# GateWay-NRF-version-puissance.net
KiCad netlist of a schematic drawn in Altium Designer
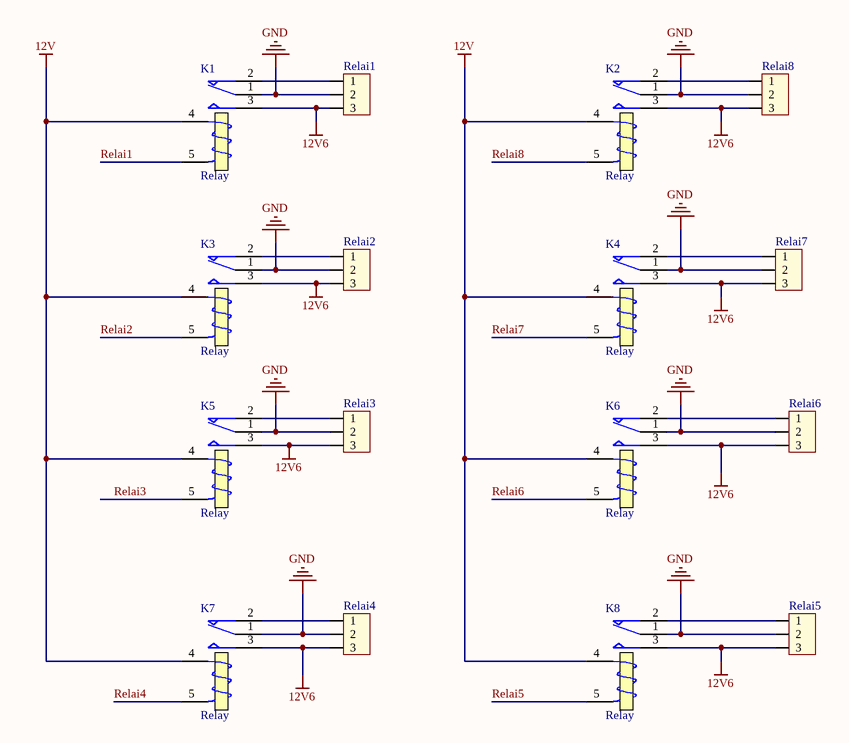
[diagram p0: GateWay-NRF-version-puissance.SchDoc]

(export (version "E")
  (design (tool "Eeschema 10.0.6"))
  (components
    (comp (ref "K1")
      (value "Relay")
      (footprint "MODULE5B")
      (description "SPDT Relay")
      (fields (field (name "PUBLISHER") "Altium Limited"))
      (libsource (lib "Miscellaneous Devices") (part "Relay"))
    )
    (comp (ref "K2")
      (value "Relay")
      (footprint "MODULE5B")
      (description "SPDT Relay")
      (fields (field (name "PUBLISHER") "Altium Limited"))
      (libsource (lib "Miscellaneous Devices") (part "Relay"))
    )
    (comp (ref "K3")
      (value "Relay")
      (footprint "MODULE5B")
      (description "SPDT Relay")
      (fields (field (name "PUBLISHER") "Altium Limited"))
      (libsource (lib "Miscellaneous Devices") (part "Relay"))
    )
    (comp (ref "K4")
      (value "Relay")
      (footprint "MODULE5B")
      (description "SPDT Relay")
      (fields (field (name "PUBLISHER") "Altium Limited"))
      (libsource (lib "Miscellaneous Devices") (part "Relay"))
    )
    (comp (ref "K5")
      (value "Relay")
      (footprint "MODULE5B")
      (description "SPDT Relay")
      (fields (field (name "PUBLISHER") "Altium Limited"))
      (libsource (lib "Miscellaneous Devices") (part "Relay"))
    )
    (comp (ref "K6")
      (value "Relay")
      (footprint "MODULE5B")
      (description "SPDT Relay")
      (fields (field (name "PUBLISHER") "Altium Limited"))
      (libsource (lib "Miscellaneous Devices") (part "Relay"))
    )
    (comp (ref "K7")
      (value "Relay")
      (footprint "MODULE5B")
      (description "SPDT Relay")
      (fields (field (name "PUBLISHER") "Altium Limited"))
      (libsource (lib "Miscellaneous Devices") (part "Relay"))
    )
    (comp (ref "K8")
      (value "Relay")
      (footprint "MODULE5B")
      (description "SPDT Relay")
      (fields (field (name "PUBLISHER") "Altium Limited"))
      (libsource (lib "Miscellaneous Devices") (part "Relay"))
    )
    (comp (ref "Relai1")
      (value "Header 3")
      (footprint "HED3")
      (description "Header 3 (Green)")
      (libsource (lib "hanguyen") (part "Hed3"))
    )
    (comp (ref "Relai2")
      (value "Header 3")
      (footprint "HED3")
      (description "Header 3 (Green)")
      (libsource (lib "hanguyen") (part "Hed3"))
    )
    (comp (ref "Relai3")
      (value "Header 3")
      (footprint "HED3")
      (description "Header 3 (Green)")
      (libsource (lib "hanguyen") (part "Hed3"))
    )
    (comp (ref "Relai4")
      (value "Header 3")
      (footprint "HED3")
      (description "Header 3 (Green)")
      (libsource (lib "hanguyen") (part "Hed3"))
    )
    (comp (ref "Relai5")
      (value "Header 3")
      (footprint "HED3")
      (description "Header 3 (Green)")
      (libsource (lib "hanguyen") (part "Hed3"))
    )
    (comp (ref "Relai6")
      (value "Header 3")
      (footprint "HED3")
      (description "Header 3 (Green)")
      (libsource (lib "hanguyen") (part "Hed3"))
    )
    (comp (ref "Relai7")
      (value "Header 3")
      (footprint "HED3")
      (description "Header 3 (Green)")
      (libsource (lib "hanguyen") (part "Hed3"))
    )
    (comp (ref "Relai8")
      (value "Header 3")
      (footprint "HED3")
      (description "Header 3 (Green)")
      (libsource (lib "hanguyen") (part "Hed3"))
    )
  )
  (nets
    (net (code "1") (name "/Relai1") (class "Default")
      (node (ref "K1") (pin "5") (pinfunction "T2_5") (pintype "passive"))
    )
    (net (code "2") (name "/Relai2") (class "Default")
      (node (ref "K3") (pin "5") (pinfunction "T2_5") (pintype "passive"))
    )
    (net (code "3") (name "/Relai3") (class "Default")
      (node (ref "K5") (pin "5") (pinfunction "T2_5") (pintype "passive"))
    )
    (net (code "4") (name "/Relai4") (class "Default")
      (node (ref "K7") (pin "5") (pinfunction "T2_5") (pintype "passive"))
    )
    (net (code "5") (name "/Relai5") (class "Default")
      (node (ref "K8") (pin "5") (pinfunction "T2_5") (pintype "passive"))
    )
    (net (code "6") (name "/Relai6") (class "Default")
      (node (ref "K6") (pin "5") (pinfunction "T2_5") (pintype "passive"))
    )
    (net (code "7") (name "/Relai7") (class "Default")
      (node (ref "K4") (pin "5") (pinfunction "T2_5") (pintype "passive"))
    )
    (net (code "8") (name "/Relai8") (class "Default")
      (node (ref "K2") (pin "5") (pinfunction "T2_5") (pintype "passive"))
    )
    (net (code "9") (name "12V") (class "Default")
      (node (ref "K1") (pin "4") (pinfunction "T1_4") (pintype "passive"))
      (node (ref "K2") (pin "4") (pinfunction "T1_4") (pintype "passive"))
      (node (ref "K3") (pin "4") (pinfunction "T1_4") (pintype "passive"))
      (node (ref "K4") (pin "4") (pinfunction "T1_4") (pintype "passive"))
      (node (ref "K5") (pin "4") (pinfunction "T1_4") (pintype "passive"))
      (node (ref "K6") (pin "4") (pinfunction "T1_4") (pintype "passive"))
      (node (ref "K7") (pin "4") (pinfunction "T1_4") (pintype "passive"))
      (node (ref "K8") (pin "4") (pinfunction "T1_4") (pintype "passive"))
    )
    (net (code "10") (name "12V6") (class "Default")
      (node (ref "K1") (pin "3") (pinfunction "NO_3") (pintype "passive"))
      (node (ref "K2") (pin "3") (pinfunction "NO_3") (pintype "passive"))
      (node (ref "K3") (pin "3") (pinfunction "NO_3") (pintype "passive"))
      (node (ref "K4") (pin "3") (pinfunction "NO_3") (pintype "passive"))
      (node (ref "K5") (pin "3") (pinfunction "NO_3") (pintype "passive"))
      (node (ref "K6") (pin "3") (pinfunction "NO_3") (pintype "passive"))
      (node (ref "K7") (pin "3") (pinfunction "NO_3") (pintype "passive"))
      (node (ref "K8") (pin "3") (pinfunction "NO_3") (pintype "passive"))
      (node (ref "Relai1") (pin "3") (pinfunction "3_3") (pintype "passive"))
      (node (ref "Relai2") (pin "3") (pinfunction "3_3") (pintype "passive"))
      (node (ref "Relai3") (pin "3") (pinfunction "3_3") (pintype "passive"))
      (node (ref "Relai4") (pin "3") (pinfunction "3_3") (pintype "passive"))
      (node (ref "Relai5") (pin "3") (pinfunction "3_3") (pintype "passive"))
      (node (ref "Relai6") (pin "3") (pinfunction "3_3") (pintype "passive"))
      (node (ref "Relai7") (pin "3") (pinfunction "3_3") (pintype "passive"))
      (node (ref "Relai8") (pin "3") (pinfunction "3_3") (pintype "passive"))
    )
    (net (code "11") (name "GND") (class "Default")
      (node (ref "K1") (pin "1") (pinfunction "COM_1") (pintype "passive"))
      (node (ref "K2") (pin "1") (pinfunction "COM_1") (pintype "passive"))
      (node (ref "K3") (pin "1") (pinfunction "COM_1") (pintype "passive"))
      (node (ref "K4") (pin "1") (pinfunction "COM_1") (pintype "passive"))
      (node (ref "K5") (pin "1") (pinfunction "COM_1") (pintype "passive"))
      (node (ref "K6") (pin "1") (pinfunction "COM_1") (pintype "passive"))
      (node (ref "K7") (pin "1") (pinfunction "COM_1") (pintype "passive"))
      (node (ref "K8") (pin "1") (pinfunction "COM_1") (pintype "passive"))
      (node (ref "Relai1") (pin "2") (pinfunction "2_2") (pintype "passive"))
      (node (ref "Relai2") (pin "2") (pinfunction "2_2") (pintype "passive"))
      (node (ref "Relai3") (pin "2") (pinfunction "2_2") (pintype "passive"))
      (node (ref "Relai4") (pin "2") (pinfunction "2_2") (pintype "passive"))
      (node (ref "Relai5") (pin "2") (pinfunction "2_2") (pintype "passive"))
      (node (ref "Relai6") (pin "2") (pinfunction "2_2") (pintype "passive"))
      (node (ref "Relai7") (pin "2") (pinfunction "2_2") (pintype "passive"))
      (node (ref "Relai8") (pin "2") (pinfunction "2_2") (pintype "passive"))
    )
    (net (code "12") (name "Net-(K1-NC)") (class "Default")
      (node (ref "K1") (pin "2") (pinfunction "NC_2") (pintype "passive"))
      (node (ref "Relai1") (pin "1") (pinfunction "1_1") (pintype "passive"))
    )
    (net (code "13") (name "Net-(K2-NC)") (class "Default")
      (node (ref "K2") (pin "2") (pinfunction "NC_2") (pintype "passive"))
      (node (ref "Relai8") (pin "1") (pinfunction "1_1") (pintype "passive"))
    )
    (net (code "14") (name "Net-(K3-NC)") (class "Default")
      (node (ref "K3") (pin "2") (pinfunction "NC_2") (pintype "passive"))
      (node (ref "Relai2") (pin "1") (pinfunction "1_1") (pintype "passive"))
    )
    (net (code "15") (name "Net-(K4-NC)") (class "Default")
      (node (ref "K4") (pin "2") (pinfunction "NC_2") (pintype "passive"))
      (node (ref "Relai7") (pin "1") (pinfunction "1_1") (pintype "passive"))
    )
    (net (code "16") (name "Net-(K5-NC)") (class "Default")
      (node (ref "K5") (pin "2") (pinfunction "NC_2") (pintype "passive"))
      (node (ref "Relai3") (pin "1") (pinfunction "1_1") (pintype "passive"))
    )
    (net (code "17") (name "Net-(K6-NC)") (class "Default")
      (node (ref "K6") (pin "2") (pinfunction "NC_2") (pintype "passive"))
      (node (ref "Relai6") (pin "1") (pinfunction "1_1") (pintype "passive"))
    )
    (net (code "18") (name "Net-(K7-NC)") (class "Default")
      (node (ref "K7") (pin "2") (pinfunction "NC_2") (pintype "passive"))
      (node (ref "Relai4") (pin "1") (pinfunction "1_1") (pintype "passive"))
    )
    (net (code "19") (name "Net-(K8-NC)") (class "Default")
      (node (ref "K8") (pin "2") (pinfunction "NC_2") (pintype "passive"))
      (node (ref "Relai5") (pin "1") (pinfunction "1_1") (pintype "passive"))
    )
  )
)
